# SHT15.net
KiCad netlist of a schematic drawn in EAGLE
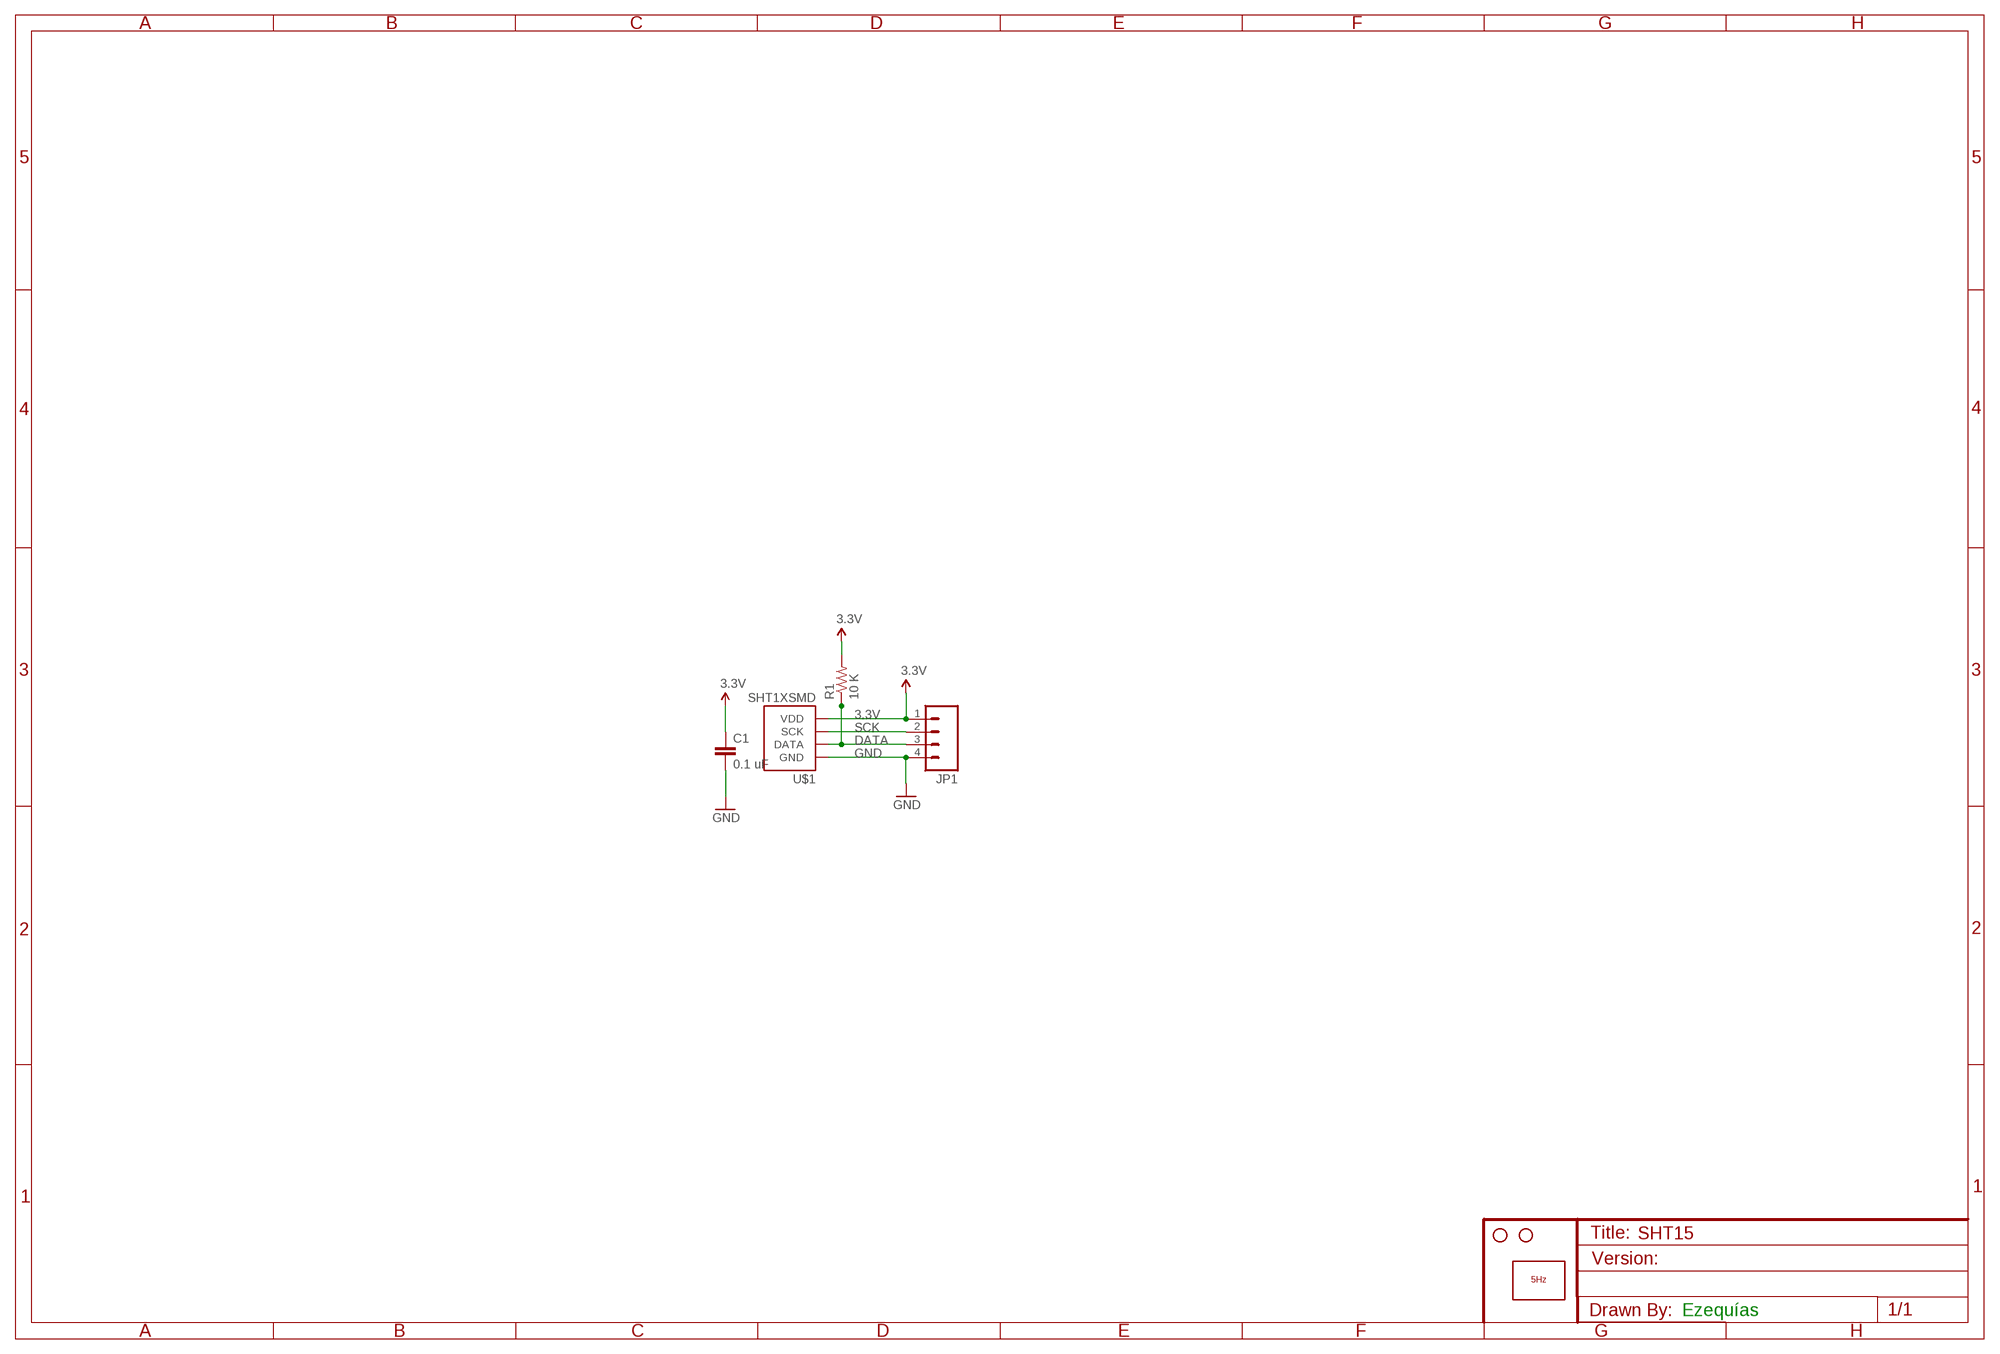
[diagram p0: schematic, sheet 1]

(export (version "E")
  (design (tool "Eeschema 10.0.6"))
  (components
    (comp (ref "C1")
      (value "0.1 uF")
      (footprint "eagle-import:0603-CAP")
      (libsource (lib "eagle-import") (part "CAP0603-CAP"))
    )
    (comp (ref "JP1")
      (value "M04PTH")
      (footprint "eagle-import:1X04")
      (libsource (lib "eagle-import") (part "M04PTH"))
    )
    (comp (ref "JP2")
      (value "STAND-OFF")
      (footprint "eagle-import:STAND-OFF")
      (libsource (lib "eagle-import") (part "STAND-OFF"))
    )
    (comp (ref "JP3")
      (value "STAND-OFF")
      (footprint "eagle-import:STAND-OFF")
      (libsource (lib "eagle-import") (part "STAND-OFF"))
    )
    (comp (ref "LOGO1")
      (value "LOGO_5HZ_H_10MM")
      (footprint "eagle-import:5HZ_LOGO_H_10MM")
      (libsource (lib "eagle-import") (part "LOGO_5HZ_H_10MM"))
    )
    (comp (ref "R1")
      (value "10 K")
      (footprint "eagle-import:0603-RES")
      (libsource (lib "eagle-import") (part "RESISTOR0603-RES"))
    )
    (comp (ref "U$1")
      (value "SHT1XSMD")
      (footprint "eagle-import:SHT1X")
      (libsource (lib "eagle-import") (part "SHT1XSMD"))
    )
  )
  (nets
    (net (code "1") (name "/DATA") (class "Default")
      (node (ref "JP1") (pin "3") (pinfunction "3_3") (pintype "passive"))
      (node (ref "R1") (pin "1") (pinfunction "1_1") (pintype "passive"))
      (node (ref "U$1") (pin "2") (pinfunction "DATA_2") (pintype "bidirectional"))
    )
    (net (code "2") (name "/SCK") (class "Default")
      (node (ref "JP1") (pin "2") (pinfunction "2_2") (pintype "passive"))
      (node (ref "U$1") (pin "3") (pinfunction "SCK_3") (pintype "input"))
    )
    (net (code "3") (name "3.3V") (class "Default")
      (node (ref "C1") (pin "1") (pinfunction "1_1") (pintype "passive"))
      (node (ref "JP1") (pin "1") (pinfunction "1_1") (pintype "passive"))
      (node (ref "R1") (pin "2") (pinfunction "2_2") (pintype "passive"))
      (node (ref "U$1") (pin "4") (pinfunction "VDD_4") (pintype "power_in"))
    )
    (net (code "4") (name "GND") (class "Default")
      (node (ref "C1") (pin "2") (pinfunction "2_2") (pintype "passive"))
      (node (ref "JP1") (pin "4") (pinfunction "4_4") (pintype "passive"))
      (node (ref "U$1") (pin "1") (pinfunction "GND_1") (pintype "power_in"))
    )
  )
)
